# MAXREFDES98_Schematic.net
KiCad netlist of a schematic drawn in EAGLE
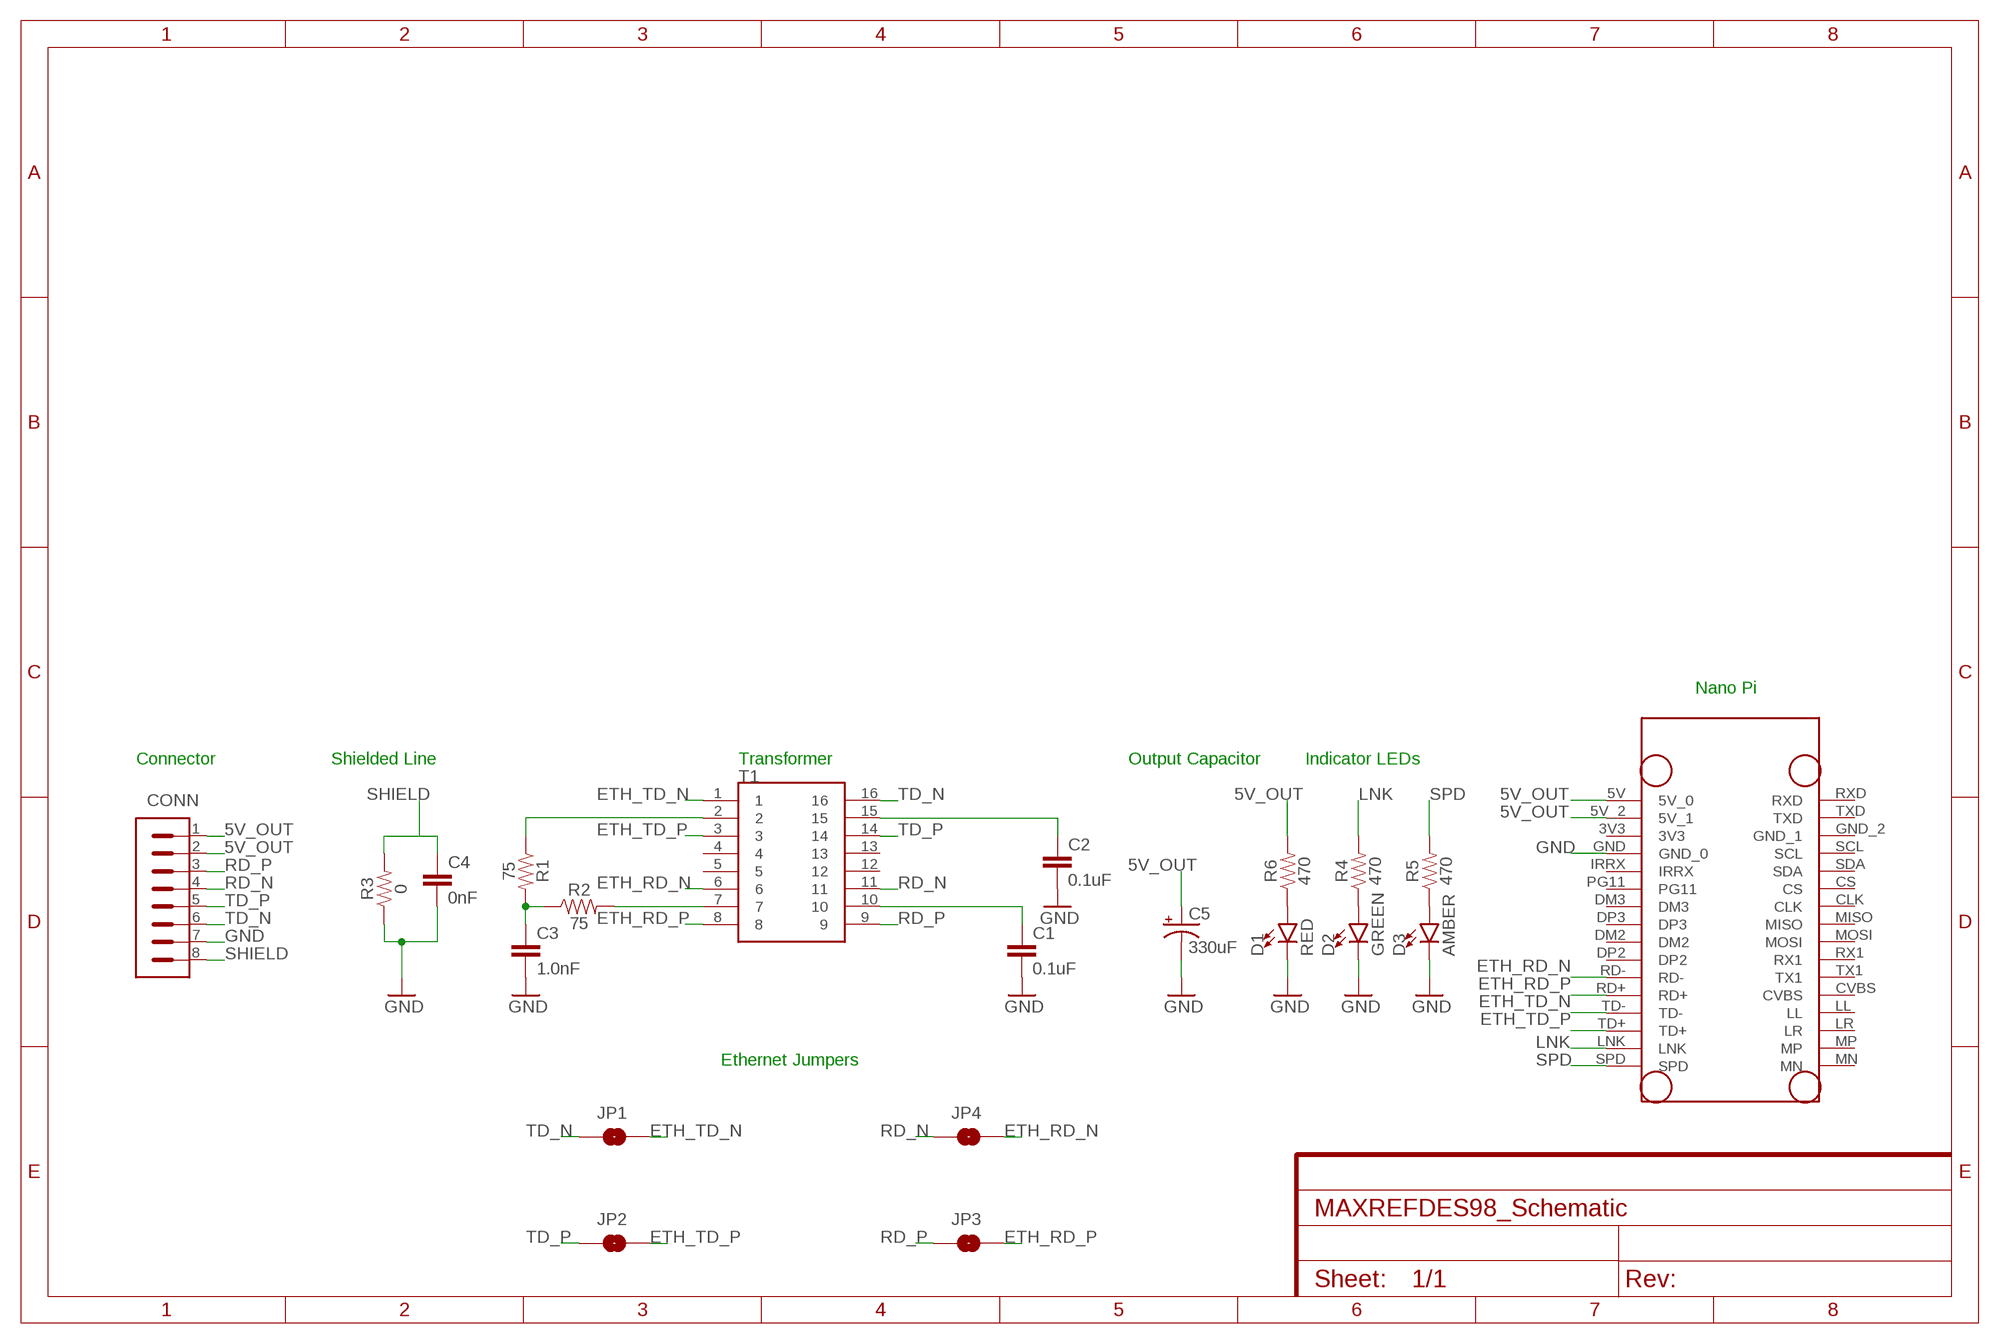
[diagram p0: schematic, sheet 1]

(export (version "E")
  (design (tool "Eeschema 10.0.6"))
  (components
    (comp (ref "C1")
      (value "0.1uF")
      (footprint "eagle-import:0603")
      (libsource (lib "eagle-import") (part "0.1UF-0603-25V-(+80/-20%)"))
    )
    (comp (ref "C2")
      (value "0.1uF")
      (footprint "eagle-import:0603")
      (libsource (lib "eagle-import") (part "0.1UF-0603-25V-(+80/-20%)"))
    )
    (comp (ref "C3")
      (value "1.0nF")
      (footprint "eagle-import:1206")
      (libsource (lib "eagle-import") (part "1.0UF-1206-50V-10%"))
    )
    (comp (ref "C4")
      (value "0nF")
      (footprint "eagle-import:0603")
      (libsource (lib "eagle-import") (part "3.3NF-0603-100V-10%"))
    )
    (comp (ref "C5")
      (value "337AXZ025M")
      (footprint "eagle-import:337AXZ025M")
      (libsource (lib "eagle-import") (part "337AXZ025M"))
    )
    (comp (ref "CONN")
      (value "PXC-8-RA-1778683")
      (footprint "eagle-import:PXC-8-RA-1778683")
      (libsource (lib "eagle-import") (part "PXC-8-RA-1778683"))
    )
    (comp (ref "D1")
      (value "RED")
      (footprint "eagle-import:FKIT-LED-1206")
      (libsource (lib "eagle-import") (part "LED-FKIT-1206"))
    )
    (comp (ref "D2")
      (value "GREEN")
      (footprint "eagle-import:FKIT-LED-1206")
      (libsource (lib "eagle-import") (part "LED-FKIT-1206"))
    )
    (comp (ref "D3")
      (value "AMBER")
      (footprint "eagle-import:FKIT-LED-1206")
      (libsource (lib "eagle-import") (part "LED-FKIT-1206"))
    )
    (comp (ref "JP1")
      (value "JUMPER-SMT_2_NO_NO-SILK")
      (footprint "eagle-import:SMT-JUMPER_2_NO_NO-SILK")
      (libsource (lib "eagle-import") (part "JUMPER-SMT_2_NO_NO-SILK"))
    )
    (comp (ref "JP2")
      (value "JUMPER-SMT_2_NO_NO-SILK")
      (footprint "eagle-import:SMT-JUMPER_2_NO_NO-SILK")
      (libsource (lib "eagle-import") (part "JUMPER-SMT_2_NO_NO-SILK"))
    )
    (comp (ref "JP3")
      (value "JUMPER-SMT_2_NO_NO-SILK")
      (footprint "eagle-import:SMT-JUMPER_2_NO_NO-SILK")
      (libsource (lib "eagle-import") (part "JUMPER-SMT_2_NO_NO-SILK"))
    )
    (comp (ref "JP4")
      (value "JUMPER-SMT_2_NO_NO-SILK")
      (footprint "eagle-import:SMT-JUMPER_2_NO_NO-SILK")
      (libsource (lib "eagle-import") (part "JUMPER-SMT_2_NO_NO-SILK"))
    )
    (comp (ref "R1")
      (value "75")
      (footprint "eagle-import:0603")
      (libsource (lib "eagle-import") (part "75KOHM-0603-1/10W-1%"))
    )
    (comp (ref "R2")
      (value "75")
      (footprint "eagle-import:0603")
      (libsource (lib "eagle-import") (part "75KOHM-0603-1/10W-1%"))
    )
    (comp (ref "R3")
      (value "0")
      (footprint "eagle-import:0603")
      (libsource (lib "eagle-import") (part "0OHM-0603-1/10W-5%"))
    )
    (comp (ref "R4")
      (value "470")
      (footprint "eagle-import:0603")
      (libsource (lib "eagle-import") (part "0OHM-0603-1/10W-5%"))
    )
    (comp (ref "R5")
      (value "470")
      (footprint "eagle-import:0603")
      (libsource (lib "eagle-import") (part "0OHM-0603-1/10W-5%"))
    )
    (comp (ref "R6")
      (value "470")
      (footprint "eagle-import:0603")
      (libsource (lib "eagle-import") (part "0OHM-0603-1/10W-5%"))
    )
    (comp (ref "T1")
      (value "TG110-S055N2RL")
      (footprint "eagle-import:TG110-S055N2RL")
      (libsource (lib "eagle-import") (part "TG110-S055N2RL"))
    )
    (comp (ref "U$2")
      (value "NANO_PI_CLEAN")
      (footprint "eagle-import:NANO_PI_CLEAN")
      (libsource (lib "eagle-import") (part "NANO_PI_CLEAN"))
    )
  )
  (nets
    (net (code "1") (name "/5V_OUT") (class "Default")
      (node (ref "C5") (pin "PLUS") (pinfunction "+_PLUS") (pintype "passive"))
      (node (ref "CONN") (pin "1") (pinfunction "1_1") (pintype "passive"))
      (node (ref "CONN") (pin "2") (pinfunction "2_2") (pintype "passive"))
      (node (ref "R6") (pin "2") (pinfunction "2_2") (pintype "passive"))
      (node (ref "U$2") (pin "5V") (pinfunction "5V_0_5V") (pintype "bidirectional"))
      (node (ref "U$2") (pin "5V_2") (pinfunction "5V_1_5V_2") (pintype "bidirectional"))
    )
    (net (code "2") (name "/ETH_RD_N") (class "Default")
      (node (ref "JP4") (pin "2") (pinfunction "2_2") (pintype "passive"))
      (node (ref "T1") (pin "6") (pinfunction "6_6") (pintype "bidirectional"))
      (node (ref "U$2") (pin "RD-") (pinfunction "RD-_RD-") (pintype "bidirectional"))
    )
    (net (code "3") (name "/ETH_RD_P") (class "Default")
      (node (ref "JP3") (pin "2") (pinfunction "2_2") (pintype "passive"))
      (node (ref "T1") (pin "8") (pinfunction "8_8") (pintype "bidirectional"))
      (node (ref "U$2") (pin "RD+") (pinfunction "RD+_RD+") (pintype "bidirectional"))
    )
    (net (code "4") (name "/ETH_TD_N") (class "Default")
      (node (ref "JP1") (pin "2") (pinfunction "2_2") (pintype "passive"))
      (node (ref "T1") (pin "1") (pinfunction "1_1") (pintype "bidirectional"))
      (node (ref "U$2") (pin "TD-") (pinfunction "TD-_TD-") (pintype "bidirectional"))
    )
    (net (code "5") (name "/ETH_TD_P") (class "Default")
      (node (ref "JP2") (pin "2") (pinfunction "2_2") (pintype "passive"))
      (node (ref "T1") (pin "3") (pinfunction "3_3") (pintype "bidirectional"))
      (node (ref "U$2") (pin "TD+") (pinfunction "TD+_TD+") (pintype "bidirectional"))
    )
    (net (code "6") (name "/LNK") (class "Default")
      (node (ref "R4") (pin "2") (pinfunction "2_2") (pintype "passive"))
      (node (ref "U$2") (pin "LNK") (pinfunction "LNK_LNK") (pintype "bidirectional"))
    )
    (net (code "7") (name "/RD_N") (class "Default")
      (node (ref "CONN") (pin "4") (pinfunction "4_4") (pintype "passive"))
      (node (ref "JP4") (pin "1") (pinfunction "1_1") (pintype "passive"))
      (node (ref "T1") (pin "11") (pinfunction "11_11") (pintype "bidirectional"))
    )
    (net (code "8") (name "/RD_P") (class "Default")
      (node (ref "CONN") (pin "3") (pinfunction "3_3") (pintype "passive"))
      (node (ref "JP3") (pin "1") (pinfunction "1_1") (pintype "passive"))
      (node (ref "T1") (pin "9") (pinfunction "9_9") (pintype "bidirectional"))
    )
    (net (code "9") (name "/SHIELD") (class "Default")
      (node (ref "C4") (pin "1") (pinfunction "1_1") (pintype "passive"))
      (node (ref "CONN") (pin "8") (pinfunction "8_8") (pintype "passive"))
      (node (ref "R3") (pin "2") (pinfunction "2_2") (pintype "passive"))
    )
    (net (code "10") (name "/SPD") (class "Default")
      (node (ref "R5") (pin "2") (pinfunction "2_2") (pintype "passive"))
      (node (ref "U$2") (pin "SPD") (pinfunction "SPD_SPD") (pintype "bidirectional"))
    )
    (net (code "11") (name "/TD_N") (class "Default")
      (node (ref "CONN") (pin "6") (pinfunction "6_6") (pintype "passive"))
      (node (ref "JP1") (pin "1") (pinfunction "1_1") (pintype "passive"))
      (node (ref "T1") (pin "16") (pinfunction "16_16") (pintype "bidirectional"))
    )
    (net (code "12") (name "/TD_P") (class "Default")
      (node (ref "CONN") (pin "5") (pinfunction "5_5") (pintype "passive"))
      (node (ref "JP2") (pin "1") (pinfunction "1_1") (pintype "passive"))
      (node (ref "T1") (pin "14") (pinfunction "14_14") (pintype "bidirectional"))
    )
    (net (code "13") (name "GND") (class "Default")
      (node (ref "C1") (pin "2") (pinfunction "2_2") (pintype "passive"))
      (node (ref "C2") (pin "2") (pinfunction "2_2") (pintype "passive"))
      (node (ref "C3") (pin "2") (pinfunction "2_2") (pintype "passive"))
      (node (ref "C4") (pin "2") (pinfunction "2_2") (pintype "passive"))
      (node (ref "C5") (pin "MINUS") (pinfunction "-_MINUS") (pintype "passive"))
      (node (ref "CONN") (pin "7") (pinfunction "7_7") (pintype "passive"))
      (node (ref "D1") (pin "C") (pinfunction "C_C") (pintype "passive"))
      (node (ref "D2") (pin "C") (pinfunction "C_C") (pintype "passive"))
      (node (ref "D3") (pin "C") (pinfunction "C_C") (pintype "passive"))
      (node (ref "R3") (pin "1") (pinfunction "1_1") (pintype "passive"))
      (node (ref "U$2") (pin "GND") (pinfunction "GND_0_GND") (pintype "bidirectional"))
    )
    (net (code "14") (name "Net-(C1-Pad1)") (class "Default")
      (node (ref "C1") (pin "1") (pinfunction "1_1") (pintype "passive"))
      (node (ref "T1") (pin "10") (pinfunction "10_10") (pintype "bidirectional"))
    )
    (net (code "15") (name "Net-(C2-Pad1)") (class "Default")
      (node (ref "C2") (pin "1") (pinfunction "1_1") (pintype "passive"))
      (node (ref "T1") (pin "15") (pinfunction "15_15") (pintype "bidirectional"))
    )
    (net (code "16") (name "Net-(C3-Pad1)") (class "Default")
      (node (ref "C3") (pin "1") (pinfunction "1_1") (pintype "passive"))
      (node (ref "R1") (pin "2") (pinfunction "2_2") (pintype "passive"))
      (node (ref "R2") (pin "1") (pinfunction "1_1") (pintype "passive"))
    )
    (net (code "17") (name "Net-(D1-PadA)") (class "Default")
      (node (ref "D1") (pin "A") (pinfunction "A_A") (pintype "passive"))
      (node (ref "R6") (pin "1") (pinfunction "1_1") (pintype "passive"))
    )
    (net (code "18") (name "Net-(D2-PadA)") (class "Default")
      (node (ref "D2") (pin "A") (pinfunction "A_A") (pintype "passive"))
      (node (ref "R4") (pin "1") (pinfunction "1_1") (pintype "passive"))
    )
    (net (code "19") (name "Net-(D3-PadA)") (class "Default")
      (node (ref "D3") (pin "A") (pinfunction "A_A") (pintype "passive"))
      (node (ref "R5") (pin "1") (pinfunction "1_1") (pintype "passive"))
    )
    (net (code "20") (name "Net-(R1-Pad1)") (class "Default")
      (node (ref "R1") (pin "1") (pinfunction "1_1") (pintype "passive"))
      (node (ref "T1") (pin "2") (pinfunction "2_2") (pintype "bidirectional"))
    )
    (net (code "21") (name "Net-(R2-Pad2)") (class "Default")
      (node (ref "R2") (pin "2") (pinfunction "2_2") (pintype "passive"))
      (node (ref "T1") (pin "7") (pinfunction "7_7") (pintype "bidirectional"))
    )
    (net (code "22") (name "unconnected-(T1-Pad4)") (class "Default")
      (node (ref "T1") (pin "4") (pinfunction "4_4") (pintype "bidirectional"))
    )
    (net (code "23") (name "unconnected-(T1-Pad5)") (class "Default")
      (node (ref "T1") (pin "5") (pinfunction "5_5") (pintype "bidirectional"))
    )
    (net (code "24") (name "unconnected-(T1-Pad12)") (class "Default")
      (node (ref "T1") (pin "12") (pinfunction "12_12") (pintype "bidirectional"))
    )
    (net (code "25") (name "unconnected-(T1-Pad13)") (class "Default")
      (node (ref "T1") (pin "13") (pinfunction "13_13") (pintype "bidirectional"))
    )
    (net (code "26") (name "unconnected-(U$2-GND_1-PadGND_2)") (class "Default")
      (node (ref "U$2") (pin "GND_2") (pinfunction "GND_1_GND_2") (pintype "bidirectional"))
    )
    (net (code "27") (name "unconnected-(U$2-Pad3V3)") (class "Default")
      (node (ref "U$2") (pin "3V3") (pinfunction "3V3_3V3") (pintype "bidirectional"))
    )
    (net (code "28") (name "unconnected-(U$2-PadCLK)") (class "Default")
      (node (ref "U$2") (pin "CLK") (pinfunction "CLK_CLK") (pintype "bidirectional"))
    )
    (net (code "29") (name "unconnected-(U$2-PadCS)") (class "Default")
      (node (ref "U$2") (pin "CS") (pinfunction "CS_CS") (pintype "bidirectional"))
    )
    (net (code "30") (name "unconnected-(U$2-PadCVBS)") (class "Default")
      (node (ref "U$2") (pin "CVBS") (pinfunction "CVBS_CVBS") (pintype "bidirectional"))
    )
    (net (code "31") (name "unconnected-(U$2-PadDM2)") (class "Default")
      (node (ref "U$2") (pin "DM2") (pinfunction "DM2_DM2") (pintype "bidirectional"))
    )
    (net (code "32") (name "unconnected-(U$2-PadDM3)") (class "Default")
      (node (ref "U$2") (pin "DM3") (pinfunction "DM3_DM3") (pintype "bidirectional"))
    )
    (net (code "33") (name "unconnected-(U$2-PadDP2)") (class "Default")
      (node (ref "U$2") (pin "DP2") (pinfunction "DP2_DP2") (pintype "bidirectional"))
    )
    (net (code "34") (name "unconnected-(U$2-PadDP3)") (class "Default")
      (node (ref "U$2") (pin "DP3") (pinfunction "DP3_DP3") (pintype "bidirectional"))
    )
    (net (code "35") (name "unconnected-(U$2-PadIRRX)") (class "Default")
      (node (ref "U$2") (pin "IRRX") (pinfunction "IRRX_IRRX") (pintype "bidirectional"))
    )
    (net (code "36") (name "unconnected-(U$2-PadLL)") (class "Default")
      (node (ref "U$2") (pin "LL") (pinfunction "LL_LL") (pintype "bidirectional"))
    )
    (net (code "37") (name "unconnected-(U$2-PadLR)") (class "Default")
      (node (ref "U$2") (pin "LR") (pinfunction "LR_LR") (pintype "bidirectional"))
    )
    (net (code "38") (name "unconnected-(U$2-PadMISO)") (class "Default")
      (node (ref "U$2") (pin "MISO") (pinfunction "MISO_MISO") (pintype "bidirectional"))
    )
    (net (code "39") (name "unconnected-(U$2-PadMN)") (class "Default")
      (node (ref "U$2") (pin "MN") (pinfunction "MN_MN") (pintype "bidirectional"))
    )
    (net (code "40") (name "unconnected-(U$2-PadMOSI)") (class "Default")
      (node (ref "U$2") (pin "MOSI") (pinfunction "MOSI_MOSI") (pintype "bidirectional"))
    )
    (net (code "41") (name "unconnected-(U$2-PadMP)") (class "Default")
      (node (ref "U$2") (pin "MP") (pinfunction "MP_MP") (pintype "bidirectional"))
    )
    (net (code "42") (name "unconnected-(U$2-PadPG11)") (class "Default")
      (node (ref "U$2") (pin "PG11") (pinfunction "PG11_PG11") (pintype "bidirectional"))
    )
    (net (code "43") (name "unconnected-(U$2-PadRX1)") (class "Default")
      (node (ref "U$2") (pin "RX1") (pinfunction "RX1_RX1") (pintype "bidirectional"))
    )
    (net (code "44") (name "unconnected-(U$2-PadRXD)") (class "Default")
      (node (ref "U$2") (pin "RXD") (pinfunction "RXD_RXD") (pintype "bidirectional"))
    )
    (net (code "45") (name "unconnected-(U$2-PadSCL)") (class "Default")
      (node (ref "U$2") (pin "SCL") (pinfunction "SCL_SCL") (pintype "bidirectional"))
    )
    (net (code "46") (name "unconnected-(U$2-PadSDA)") (class "Default")
      (node (ref "U$2") (pin "SDA") (pinfunction "SDA_SDA") (pintype "bidirectional"))
    )
    (net (code "47") (name "unconnected-(U$2-PadTX1)") (class "Default")
      (node (ref "U$2") (pin "TX1") (pinfunction "TX1_TX1") (pintype "bidirectional"))
    )
    (net (code "48") (name "unconnected-(U$2-PadTXD)") (class "Default")
      (node (ref "U$2") (pin "TXD") (pinfunction "TXD_TXD") (pintype "bidirectional"))
    )
  )
)
